# 8_-_DAC_And_MIC.net
KiCad netlist of a schematic drawn in Altium Designer
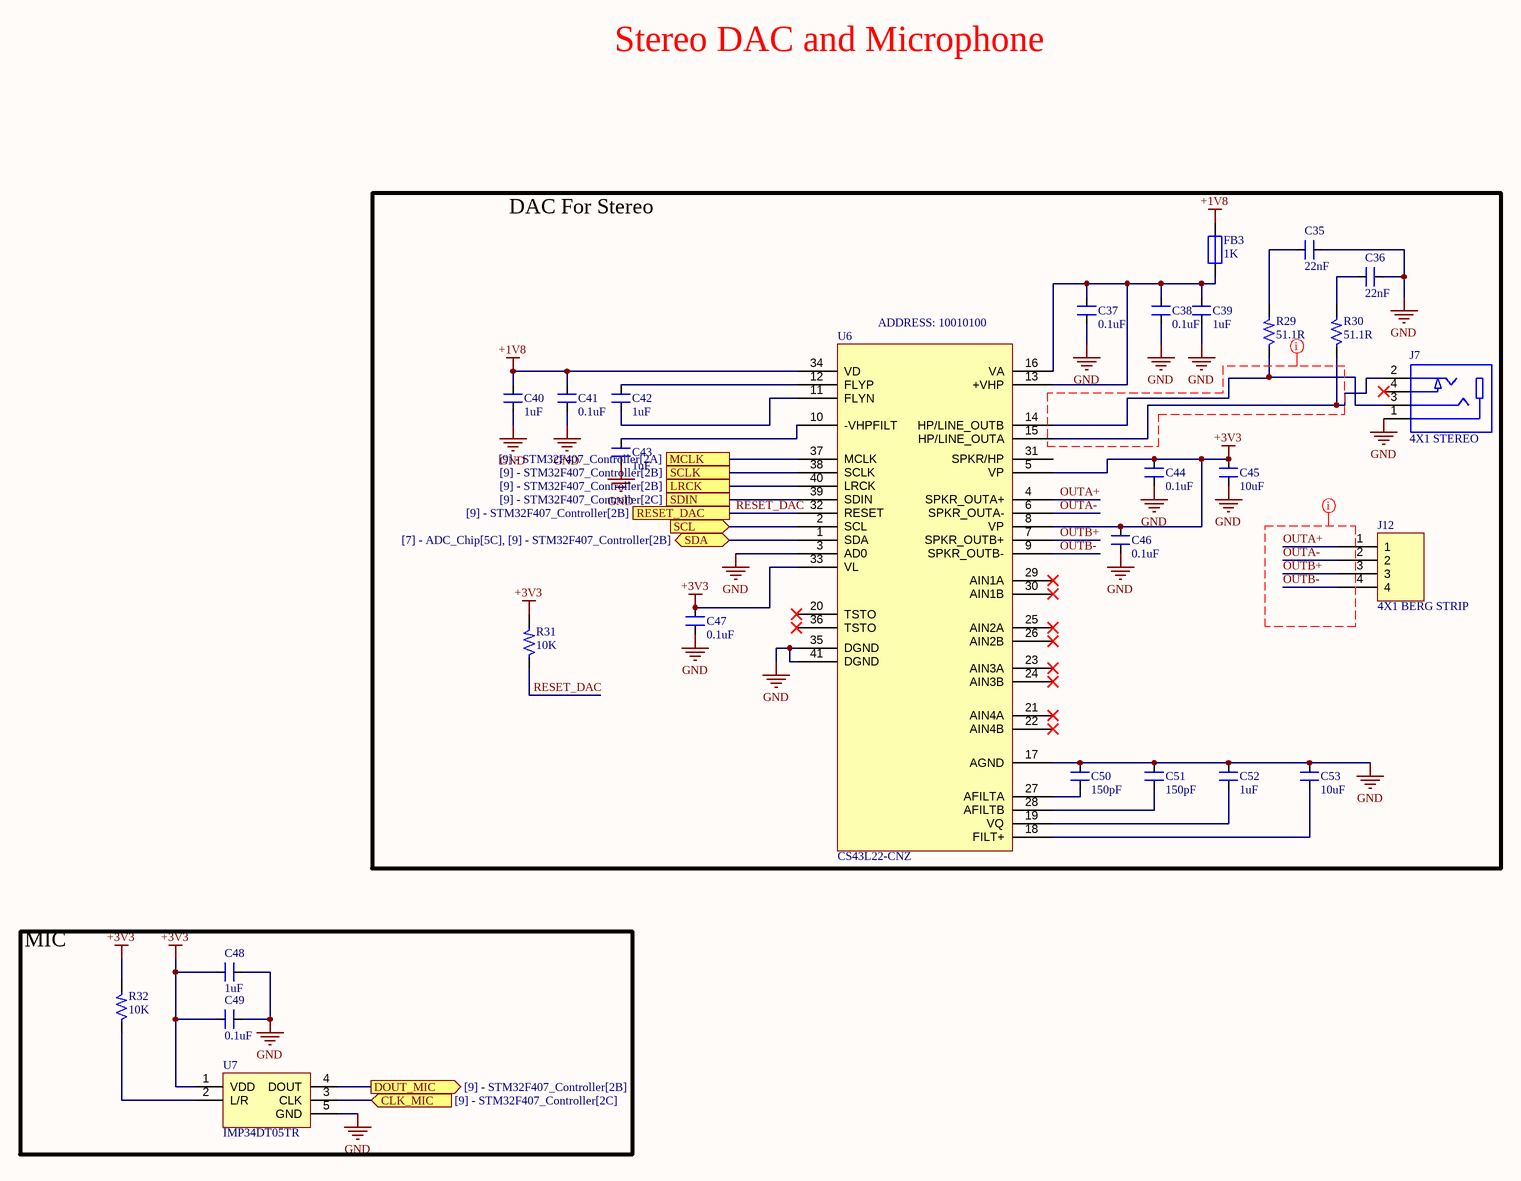
[diagram p0: [8] - DAC_And_MIC.SchDoc]

(export (version "E")
  (design (tool "Eeschema 10.0.6"))
  (components
    (comp (ref "C35")
      (value "22nF")
      (footprint "CAP_0805")
      (description "0.022µF ±10% 50V Ceramic Capacitor X7R 0805 (2012 Metric)")
      (fields
        (field (name "MANUFACTURER") "Samsung Electro-Mechanics")
        (field (name "MANUFACTURER PART NUMBER") "CL21B223KBANNNC")
      )
      (libsource (lib "ESTEEMPCBLIB") (part "CAP_22nF-50V-10%-0805"))
    )
    (comp (ref "C36")
      (value "22nF")
      (footprint "CAP_0805")
      (description "0.022µF ±10% 50V Ceramic Capacitor X7R 0805 (2012 Metric)")
      (fields
        (field (name "MANUFACTURER") "Samsung Electro-Mechanics")
        (field (name "MANUFACTURER PART NUMBER") "CL21B223KBANNNC")
      )
      (libsource (lib "ESTEEMPCBLIB") (part "CAP_22nF-50V-10%-0805"))
    )
    (comp (ref "C37")
      (value "0.1uF")
      (footprint "CAP_0805")
      (description "0.1µF ±5% 50V Ceramic Capacitor X7R 0805 (2012 Metric)")
      (fields
        (field (name "MANUFACTURER") "AVX Corporation")
        (field (name "MANUFACTURER PART NUMBER") "08055C104JAT4A")
      )
      (libsource (lib "ESTEEMPCBLIB") (part "CAP_0.1uF-50V-5%-0805"))
    )
    (comp (ref "C38")
      (value "0.1uF")
      (footprint "CAP_0805")
      (description "0.1µF ±5% 50V Ceramic Capacitor X7R 0805 (2012 Metric)")
      (fields
        (field (name "MANUFACTURER") "AVX Corporation")
        (field (name "MANUFACTURER PART NUMBER") "08055C104JAT4A")
      )
      (libsource (lib "ESTEEMPCBLIB") (part "CAP_0.1uF-50V-5%-0805"))
    )
    (comp (ref "C39")
      (value "1uF")
      (footprint "CAP_0805")
      (description "1µF ±5% 50V Ceramic Capacitor X7R 0805 (2012 Metric)")
      (fields
        (field (name "MANUFACTURER") "Samsung")
        (field (name "MANUFACTURER PART NUMBER") "CC0805JKX7R9BB105")
      )
      (libsource (lib "ESTEEMPCBLIB") (part "CAP_1uF-50V-5%-0805"))
    )
    (comp (ref "C40")
      (value "1uF")
      (footprint "CAP_0805")
      (description "1µF ±5% 50V Ceramic Capacitor X7R 0805 (2012 Metric)")
      (fields
        (field (name "MANUFACTURER") "Samsung")
        (field (name "MANUFACTURER PART NUMBER") "CC0805JKX7R9BB105")
      )
      (libsource (lib "ESTEEMPCBLIB") (part "CAP_1uF-50V-5%-0805"))
    )
    (comp (ref "C41")
      (value "0.1uF")
      (footprint "CAP_0805")
      (description "0.1µF ±5% 50V Ceramic Capacitor X7R 0805 (2012 Metric)")
      (fields
        (field (name "MANUFACTURER") "AVX Corporation")
        (field (name "MANUFACTURER PART NUMBER") "08055C104JAT4A")
      )
      (libsource (lib "ESTEEMPCBLIB") (part "CAP_0.1uF-50V-5%-0805"))
    )
    (comp (ref "C42")
      (value "1uF")
      (footprint "CAP_0805")
      (description "1µF ±5% 50V Ceramic Capacitor X7R 0805 (2012 Metric)")
      (fields
        (field (name "MANUFACTURER") "Samsung")
        (field (name "MANUFACTURER PART NUMBER") "CC0805JKX7R9BB105")
      )
      (libsource (lib "ESTEEMPCBLIB") (part "CAP_1uF-50V-5%-0805"))
    )
    (comp (ref "C43")
      (value "1uF")
      (footprint "CAP_0805")
      (description "1µF ±5% 50V Ceramic Capacitor X7R 0805 (2012 Metric)")
      (fields
        (field (name "MANUFACTURER") "Samsung")
        (field (name "MANUFACTURER PART NUMBER") "CC0805JKX7R9BB105")
      )
      (libsource (lib "ESTEEMPCBLIB") (part "CAP_1uF-50V-5%-0805"))
    )
    (comp (ref "C44")
      (value "0.1uF")
      (footprint "CAP_0805")
      (description "0.1µF ±5% 50V Ceramic Capacitor X7R 0805 (2012 Metric)")
      (fields
        (field (name "MANUFACTURER") "AVX Corporation")
        (field (name "MANUFACTURER PART NUMBER") "08055C104JAT4A")
      )
      (libsource (lib "ESTEEMPCBLIB") (part "CAP_0.1uF-50V-5%-0805"))
    )
    (comp (ref "C45")
      (value "10uF")
      (footprint "CAP_1206")
      (description "10µF ±10% 50V Ceramic Capacitor X7R 1206 (3216 Metric)")
      (fields
        (field (name "MANUFACTURER") "KEMET")
        (field (name "MANUFACTURER PART NUMBER") "CL31B106KBHNNNE")
      )
      (libsource (lib "ESTEEMPCBLIB") (part "CAP_10uF-50V-10%-1206"))
    )
    (comp (ref "C46")
      (value "0.1uF")
      (footprint "CAP_0805")
      (description "0.1µF ±5% 50V Ceramic Capacitor X7R 0805 (2012 Metric)")
      (fields
        (field (name "MANUFACTURER") "AVX Corporation")
        (field (name "MANUFACTURER PART NUMBER") "08055C104JAT4A")
      )
      (libsource (lib "ESTEEMPCBLIB") (part "CAP_0.1uF-50V-5%-0805"))
    )
    (comp (ref "C47")
      (value "0.1uF")
      (footprint "CAP_0805")
      (description "0.1µF ±5% 50V Ceramic Capacitor X7R 0805 (2012 Metric)")
      (fields
        (field (name "MANUFACTURER") "AVX Corporation")
        (field (name "MANUFACTURER PART NUMBER") "08055C104JAT4A")
      )
      (libsource (lib "ESTEEMPCBLIB") (part "CAP_0.1uF-50V-5%-0805"))
    )
    (comp (ref "C48")
      (value "1uF")
      (footprint "CAP_0805")
      (description "1µF ±5% 50V Ceramic Capacitor X7R 0805 (2012 Metric)")
      (fields
        (field (name "MANUFACTURER") "Samsung")
        (field (name "MANUFACTURER PART NUMBER") "CC0805JKX7R9BB105")
      )
      (libsource (lib "ESTEEMPCBLIB") (part "CAP_1uF-50V-5%-0805"))
    )
    (comp (ref "C49")
      (value "0.1uF")
      (footprint "CAP_0805")
      (description "0.1µF ±5% 50V Ceramic Capacitor X7R 0805 (2012 Metric)")
      (fields
        (field (name "MANUFACTURER") "AVX Corporation")
        (field (name "MANUFACTURER PART NUMBER") "08055C104JAT4A")
      )
      (libsource (lib "ESTEEMPCBLIB") (part "CAP_0.1uF-50V-5%-0805"))
    )
    (comp (ref "C50")
      (value "150pF")
      (footprint "CAP_0805")
      (description "150pF ±10% 50V Ceramic Capacitor C0G, NP0 0805 (2012 Metric)")
      (fields
        (field (name "MANUFACTURER") "AVX Corporation")
        (field (name "MANUFACTURER PART NUMBER") "08055A151KAT2A")
      )
      (libsource (lib "ESTEEMPCBLIB") (part "CAP_150pF-50V-10%-0805"))
    )
    (comp (ref "C51")
      (value "150pF")
      (footprint "CAP_0805")
      (description "150pF ±10% 50V Ceramic Capacitor C0G, NP0 0805 (2012 Metric)")
      (fields
        (field (name "MANUFACTURER") "AVX Corporation")
        (field (name "MANUFACTURER PART NUMBER") "08055A151KAT2A")
      )
      (libsource (lib "ESTEEMPCBLIB") (part "CAP_150pF-50V-10%-0805"))
    )
    (comp (ref "C52")
      (value "1uF")
      (footprint "CAP_0805")
      (description "1µF ±5% 50V Ceramic Capacitor X7R 0805 (2012 Metric)")
      (fields
        (field (name "MANUFACTURER") "Samsung")
        (field (name "MANUFACTURER PART NUMBER") "CC0805JKX7R9BB105")
      )
      (libsource (lib "ESTEEMPCBLIB") (part "CAP_1uF-50V-5%-0805"))
    )
    (comp (ref "C53")
      (value "10uF")
      (footprint "CAP_1206")
      (description "10µF ±10% 50V Ceramic Capacitor X7R 1206 (3216 Metric)")
      (fields
        (field (name "MANUFACTURER") "KEMET")
        (field (name "MANUFACTURER PART NUMBER") "CL31B106KBHNNNE")
      )
      (libsource (lib "ESTEEMPCBLIB") (part "CAP_10uF-50V-10%-1206"))
    )
    (comp (ref "FB3")
      (value "1K")
      (footprint "IND_0805")
      (description "1 kOhms @ 100MHz 1 Power Line Ferrite Bead 0805 (2012 Metric) 1.6A")
      (fields
        (field (name "MANUFACTURER") "Laird")
        (field (name "MANUFACTURER PART NUMBER") "BLM21SP102SH1D")
      )
      (libsource (lib "ESTEEMPCBLIB") (part "FB_1K-100MHZ-1.6A-0805"))
    )
    (comp (ref "J7")
      (value "4X1 STEREO")
      (footprint "CON_SJ-2504A-SMT-TR_SMD")
      (fields
        (field (name "MANUFACTURER") "CUI Devices")
        (field (name "MANUFACTURER PART NUMBER") "SJ-2504A-SMT-TR")
      )
      (libsource (lib "ESTEEMPCBLIB") (part "CON-PLG-STEREO_4X1-100-RA-SMD"))
    )
    (comp (ref "J12")
      (value "4X1 BERG STRIP")
      (footprint "CON4_100_40D72_TH_ST_MALE")
      (description "4 Pins, 1 Row 2.54mm Pitch, Straight bergstrip, Male")
      (fields (field (name "MANUFACTURER") "NA"))
      (libsource (lib "ESTEEMPCBLIB") (part "CON-BS-PLG_4X1-100-ST-TH"))
    )
    (comp (ref "R29")
      (value "51.1R")
      (footprint "RES_0603")
      (description "51.1 Ohms ±1% 0.1W, 1/10W Chip Resistor 0603 (1608 Metric) Thick Film")
      (fields
        (field (name "MANUFACTURER") "Vishay Dale")
        (field (name "MANUFACTURER PART NUMBER") "CRCW060351R1FKEAC")
      )
      (libsource (lib "ESTEEMPCBLIB") (part "RES_51.1R-0.1W-1%-0603"))
    )
    (comp (ref "R30")
      (value "51.1R")
      (footprint "RES_0603")
      (description "51.1 Ohms ±1% 0.1W, 1/10W Chip Resistor 0603 (1608 Metric) Thick Film")
      (fields
        (field (name "MANUFACTURER") "Vishay Dale")
        (field (name "MANUFACTURER PART NUMBER") "CRCW060351R1FKEAC")
      )
      (libsource (lib "ESTEEMPCBLIB") (part "RES_51.1R-0.1W-1%-0603"))
    )
    (comp (ref "R31")
      (value "10K")
      (footprint "RES_0603")
      (description "10 kOhms ±1% 0.1W, 1/10W Chip Resistor 0603 (1608 Metric) Automotive AEC-Q200 Thick Film")
      (fields (field (name "MANUFACTURER") "Walsin") (field (name "MANUFACTURER PART NUMBER") "WR06X1002FTL"))
      (libsource (lib "ESTEEMPCBLIB") (part "RES_10K-0.1W-1%-0603"))
    )
    (comp (ref "R32")
      (value "10K")
      (footprint "RES_0603")
      (description "10 kOhms ±1% 0.1W, 1/10W Chip Resistor 0603 (1608 Metric) Automotive AEC-Q200 Thick Film")
      (fields (field (name "MANUFACTURER") "Walsin") (field (name "MANUFACTURER PART NUMBER") "WR06X1002FTL"))
      (libsource (lib "ESTEEMPCBLIB") (part "RES_10K-0.1W-1%-0603"))
    )
    (comp (ref "U6")
      (value "CS43L22-CNZ")
      (footprint "QFN40_19_284_33X9_SMD")
      (description "Audio D/A Converter ICs Low Power Stereo DAC w/ClassD Spkr Driver")
      (fields (field (name "MANUFACTURER") "Cirrus Logic"))
      (libsource (lib "ESTEEMPCBLIB") (part "IC_CS43L22"))
    )
    (comp (ref "U7")
      (value "IMP34DT05TR")
      (footprint "HCLGA-4_53_137_15X37_SMD")
      (description "MEMS Microphones AUTO & INDUSTRIAL SENSORS")
      (fields (field (name "MANUFACTURER") "STMicroelectronics"))
      (libsource (lib "ESTEEMPCBLIB") (part "IC_IMP34DT05TR"))
    )
  )
  (nets
    (net (code "1") (name "+1V8") (class "Default")
      (node (ref "C40") (pin "1") (pinfunction "1_1") (pintype "passive"))
      (node (ref "C41") (pin "2") (pinfunction "2_2") (pintype "passive"))
      (node (ref "FB3") (pin "2") (pinfunction "2_2") (pintype "passive"))
      (node (ref "U6") (pin "34") (pinfunction "VD_34") (pintype "passive"))
    )
    (net (code "2") (name "+3V3") (class "Default")
      (node (ref "C44") (pin "2") (pinfunction "2_2") (pintype "passive"))
      (node (ref "C45") (pin "2") (pinfunction "2_2") (pintype "passive"))
      (node (ref "C46") (pin "2") (pinfunction "2_2") (pintype "passive"))
      (node (ref "C47") (pin "2") (pinfunction "2_2") (pintype "passive"))
      (node (ref "C48") (pin "1") (pinfunction "1_1") (pintype "passive"))
      (node (ref "C49") (pin "2") (pinfunction "2_2") (pintype "passive"))
      (node (ref "R31") (pin "2") (pinfunction "2_2") (pintype "passive"))
      (node (ref "R32") (pin "2") (pinfunction "2_2") (pintype "passive"))
      (node (ref "U6") (pin "33") (pinfunction "VL_33") (pintype "passive"))
      (node (ref "U6") (pin "5") (pinfunction "VP_5") (pintype "passive"))
      (node (ref "U6") (pin "8") (pinfunction "VP_8") (pintype "passive"))
      (node (ref "U7") (pin "1") (pinfunction "VDD_1") (pintype "passive"))
    )
    (net (code "3") (name "/CLK_MIC") (class "Default")
      (node (ref "U7") (pin "3") (pinfunction "CLK_3") (pintype "passive"))
    )
    (net (code "4") (name "/DOUT_MIC") (class "Default")
      (node (ref "U7") (pin "4") (pinfunction "DOUT_4") (pintype "passive"))
    )
    (net (code "5") (name "/LRCK") (class "Default")
      (node (ref "U6") (pin "40") (pinfunction "LRCK_40") (pintype "passive"))
    )
    (net (code "6") (name "/MCLK") (class "Default")
      (node (ref "U6") (pin "37") (pinfunction "MCLK_37") (pintype "passive"))
    )
    (net (code "7") (name "/OUTA+") (class "Default")
      (node (ref "J12") (pin "1") (pinfunction "1_1") (pintype "passive"))
      (node (ref "U6") (pin "4") (pinfunction "SPKR_OUTA+_4") (pintype "passive"))
    )
    (net (code "8") (name "/OUTA-") (class "Default")
      (node (ref "J12") (pin "2") (pinfunction "2_2") (pintype "passive"))
      (node (ref "U6") (pin "6") (pinfunction "SPKR_OUTA-_6") (pintype "passive"))
    )
    (net (code "9") (name "/OUTB+") (class "Default")
      (node (ref "J12") (pin "3") (pinfunction "3_3") (pintype "passive"))
      (node (ref "U6") (pin "7") (pinfunction "SPKR_OUTB+_7") (pintype "passive"))
    )
    (net (code "10") (name "/OUTB-") (class "Default")
      (node (ref "J12") (pin "4") (pinfunction "4_4") (pintype "passive"))
      (node (ref "U6") (pin "9") (pinfunction "SPKR_OUTB-_9") (pintype "passive"))
    )
    (net (code "11") (name "/RESET_DAC") (class "Default")
      (node (ref "R31") (pin "1") (pinfunction "1_1") (pintype "passive"))
      (node (ref "U6") (pin "32") (pinfunction "RESET_32") (pintype "passive"))
    )
    (net (code "12") (name "/SCL") (class "Default")
      (node (ref "U6") (pin "2") (pinfunction "SCL_2") (pintype "passive"))
    )
    (net (code "13") (name "/SCLK") (class "Default")
      (node (ref "U6") (pin "38") (pinfunction "SCLK_38") (pintype "passive"))
    )
    (net (code "14") (name "/SDA") (class "Default")
      (node (ref "U6") (pin "1") (pinfunction "SDA_1") (pintype "passive"))
    )
    (net (code "15") (name "/SDIN") (class "Default")
      (node (ref "U6") (pin "39") (pinfunction "SDIN_39") (pintype "passive"))
    )
    (net (code "16") (name "GND") (class "Default")
      (node (ref "C35") (pin "2") (pinfunction "2_2") (pintype "passive"))
      (node (ref "C36") (pin "1") (pinfunction "1_1") (pintype "passive"))
      (node (ref "C37") (pin "1") (pinfunction "1_1") (pintype "passive"))
      (node (ref "C38") (pin "1") (pinfunction "1_1") (pintype "passive"))
      (node (ref "C39") (pin "2") (pinfunction "2_2") (pintype "passive"))
      (node (ref "C40") (pin "2") (pinfunction "2_2") (pintype "passive"))
      (node (ref "C41") (pin "1") (pinfunction "1_1") (pintype "passive"))
      (node (ref "C43") (pin "2") (pinfunction "2_2") (pintype "passive"))
      (node (ref "C44") (pin "1") (pinfunction "1_1") (pintype "passive"))
      (node (ref "C45") (pin "1") (pinfunction "1_1") (pintype "passive"))
      (node (ref "C46") (pin "1") (pinfunction "1_1") (pintype "passive"))
      (node (ref "C47") (pin "1") (pinfunction "1_1") (pintype "passive"))
      (node (ref "C48") (pin "2") (pinfunction "2_2") (pintype "passive"))
      (node (ref "C49") (pin "1") (pinfunction "1_1") (pintype "passive"))
      (node (ref "C50") (pin "2") (pinfunction "2_2") (pintype "passive"))
      (node (ref "C51") (pin "2") (pinfunction "2_2") (pintype "passive"))
      (node (ref "C52") (pin "1") (pinfunction "1_1") (pintype "passive"))
      (node (ref "C53") (pin "2") (pinfunction "2_2") (pintype "passive"))
      (node (ref "J7") (pin "1") (pinfunction "1_1") (pintype "passive"))
      (node (ref "U6") (pin "17") (pinfunction "AGND_17") (pintype "passive"))
      (node (ref "U6") (pin "3") (pinfunction "AD0_3") (pintype "passive"))
      (node (ref "U6") (pin "35") (pinfunction "DGND_35") (pintype "passive"))
      (node (ref "U6") (pin "41") (pinfunction "DGND_41") (pintype "passive"))
      (node (ref "U7") (pin "5") (pinfunction "GND_5") (pintype "passive"))
    )
    (net (code "17") (name "Net-(C35-Pad1)") (class "Default")
      (node (ref "C35") (pin "1") (pinfunction "1_1") (pintype "passive"))
      (node (ref "R29") (pin "2") (pinfunction "2_2") (pintype "passive"))
    )
    (net (code "18") (name "Net-(C36-Pad2)") (class "Default")
      (node (ref "C36") (pin "2") (pinfunction "2_2") (pintype "passive"))
      (node (ref "R30") (pin "2") (pinfunction "2_2") (pintype "passive"))
    )
    (net (code "19") (name "Net-(U6-+VHP)") (class "Default")
      (node (ref "C37") (pin "2") (pinfunction "2_2") (pintype "passive"))
      (node (ref "C38") (pin "2") (pinfunction "2_2") (pintype "passive"))
      (node (ref "C39") (pin "1") (pinfunction "1_1") (pintype "passive"))
      (node (ref "FB3") (pin "1") (pinfunction "1_1") (pintype "passive"))
      (node (ref "U6") (pin "13") (pinfunction "+VHP_13") (pintype "passive"))
      (node (ref "U6") (pin "16") (pinfunction "VA_16") (pintype "passive"))
    )
    (net (code "20") (name "Net-(U6--VHPFILT)") (class "Default")
      (node (ref "C43") (pin "1") (pinfunction "1_1") (pintype "passive"))
      (node (ref "U6") (pin "10") (pinfunction "-VHPFILT_10") (pintype "passive"))
    )
    (net (code "21") (name "Net-(U6-AFILTA)") (class "Default")
      (node (ref "C50") (pin "1") (pinfunction "1_1") (pintype "passive"))
      (node (ref "U6") (pin "27") (pinfunction "AFILTA_27") (pintype "passive"))
    )
    (net (code "22") (name "Net-(U6-AFILTB)") (class "Default")
      (node (ref "C51") (pin "1") (pinfunction "1_1") (pintype "passive"))
      (node (ref "U6") (pin "28") (pinfunction "AFILTB_28") (pintype "passive"))
    )
    (net (code "23") (name "Net-(U6-FILT+)") (class "Default")
      (node (ref "C53") (pin "1") (pinfunction "1_1") (pintype "passive"))
      (node (ref "U6") (pin "18") (pinfunction "FILT+_18") (pintype "passive"))
    )
    (net (code "24") (name "Net-(U6-FLYN)") (class "Default")
      (node (ref "C42") (pin "2") (pinfunction "2_2") (pintype "passive"))
      (node (ref "U6") (pin "11") (pinfunction "FLYN_11") (pintype "passive"))
    )
    (net (code "25") (name "Net-(U6-FLYP)") (class "Default")
      (node (ref "C42") (pin "1") (pinfunction "1_1") (pintype "passive"))
      (node (ref "U6") (pin "12") (pinfunction "FLYP_12") (pintype "passive"))
    )
    (net (code "26") (name "Net-(U6-HP{slash}LINE_OUTA)") (class "Default")
      (node (ref "J7") (pin "2") (pinfunction "2_2") (pintype "passive"))
      (node (ref "R30") (pin "1") (pinfunction "1_1") (pintype "passive"))
      (node (ref "U6") (pin "15") (pinfunction "HP/LINE_OUTA_15") (pintype "passive"))
    )
    (net (code "27") (name "Net-(U6-HP{slash}LINE_OUTB)") (class "Default")
      (node (ref "J7") (pin "3") (pinfunction "3_3") (pintype "passive"))
      (node (ref "R29") (pin "1") (pinfunction "1_1") (pintype "passive"))
      (node (ref "U6") (pin "14") (pinfunction "HP/LINE_OUTB_14") (pintype "passive"))
    )
    (net (code "28") (name "Net-(U6-VQ)") (class "Default")
      (node (ref "C52") (pin "2") (pinfunction "2_2") (pintype "passive"))
      (node (ref "U6") (pin "19") (pinfunction "VQ_19") (pintype "passive"))
    )
    (net (code "29") (name "Net-(U7-L{slash}R)") (class "Default")
      (node (ref "R32") (pin "1") (pinfunction "1_1") (pintype "passive"))
      (node (ref "U7") (pin "2") (pinfunction "L/R_2") (pintype "passive"))
    )
    (net (code "30") (name "unconnected-(J7-Pad4)") (class "Default")
      (node (ref "J7") (pin "4") (pinfunction "4_4") (pintype "passive+no_connect"))
    )
    (net (code "31") (name "unconnected-(U6-AIN1A-Pad29)") (class "Default")
      (node (ref "U6") (pin "29") (pinfunction "AIN1A_29") (pintype "passive+no_connect"))
    )
    (net (code "32") (name "unconnected-(U6-AIN1B-Pad30)") (class "Default")
      (node (ref "U6") (pin "30") (pinfunction "AIN1B_30") (pintype "passive+no_connect"))
    )
    (net (code "33") (name "unconnected-(U6-AIN2A-Pad25)") (class "Default")
      (node (ref "U6") (pin "25") (pinfunction "AIN2A_25") (pintype "passive+no_connect"))
    )
    (net (code "34") (name "unconnected-(U6-AIN2B-Pad26)") (class "Default")
      (node (ref "U6") (pin "26") (pinfunction "AIN2B_26") (pintype "passive+no_connect"))
    )
    (net (code "35") (name "unconnected-(U6-AIN3A-Pad23)") (class "Default")
      (node (ref "U6") (pin "23") (pinfunction "AIN3A_23") (pintype "passive+no_connect"))
    )
    (net (code "36") (name "unconnected-(U6-AIN3B-Pad24)") (class "Default")
      (node (ref "U6") (pin "24") (pinfunction "AIN3B_24") (pintype "passive+no_connect"))
    )
    (net (code "37") (name "unconnected-(U6-AIN4A-Pad21)") (class "Default")
      (node (ref "U6") (pin "21") (pinfunction "AIN4A_21") (pintype "passive+no_connect"))
    )
    (net (code "38") (name "unconnected-(U6-AIN4B-Pad22)") (class "Default")
      (node (ref "U6") (pin "22") (pinfunction "AIN4B_22") (pintype "passive+no_connect"))
    )
    (net (code "39") (name "unconnected-(U6-SPKR{slash}HP-Pad31)") (class "Default")
      (node (ref "U6") (pin "31") (pinfunction "SPKR/HP_31") (pintype "passive"))
    )
    (net (code "40") (name "unconnected-(U6-TSTO-Pad20)") (class "Default")
      (node (ref "U6") (pin "20") (pinfunction "TSTO_20") (pintype "passive+no_connect"))
    )
    (net (code "41") (name "unconnected-(U6-TSTO-Pad36)") (class "Default")
      (node (ref "U6") (pin "36") (pinfunction "TSTO_36") (pintype "passive+no_connect"))
    )
  )
)
